# RF-VtoI.net
KiCad netlist of a schematic drawn in EAGLE
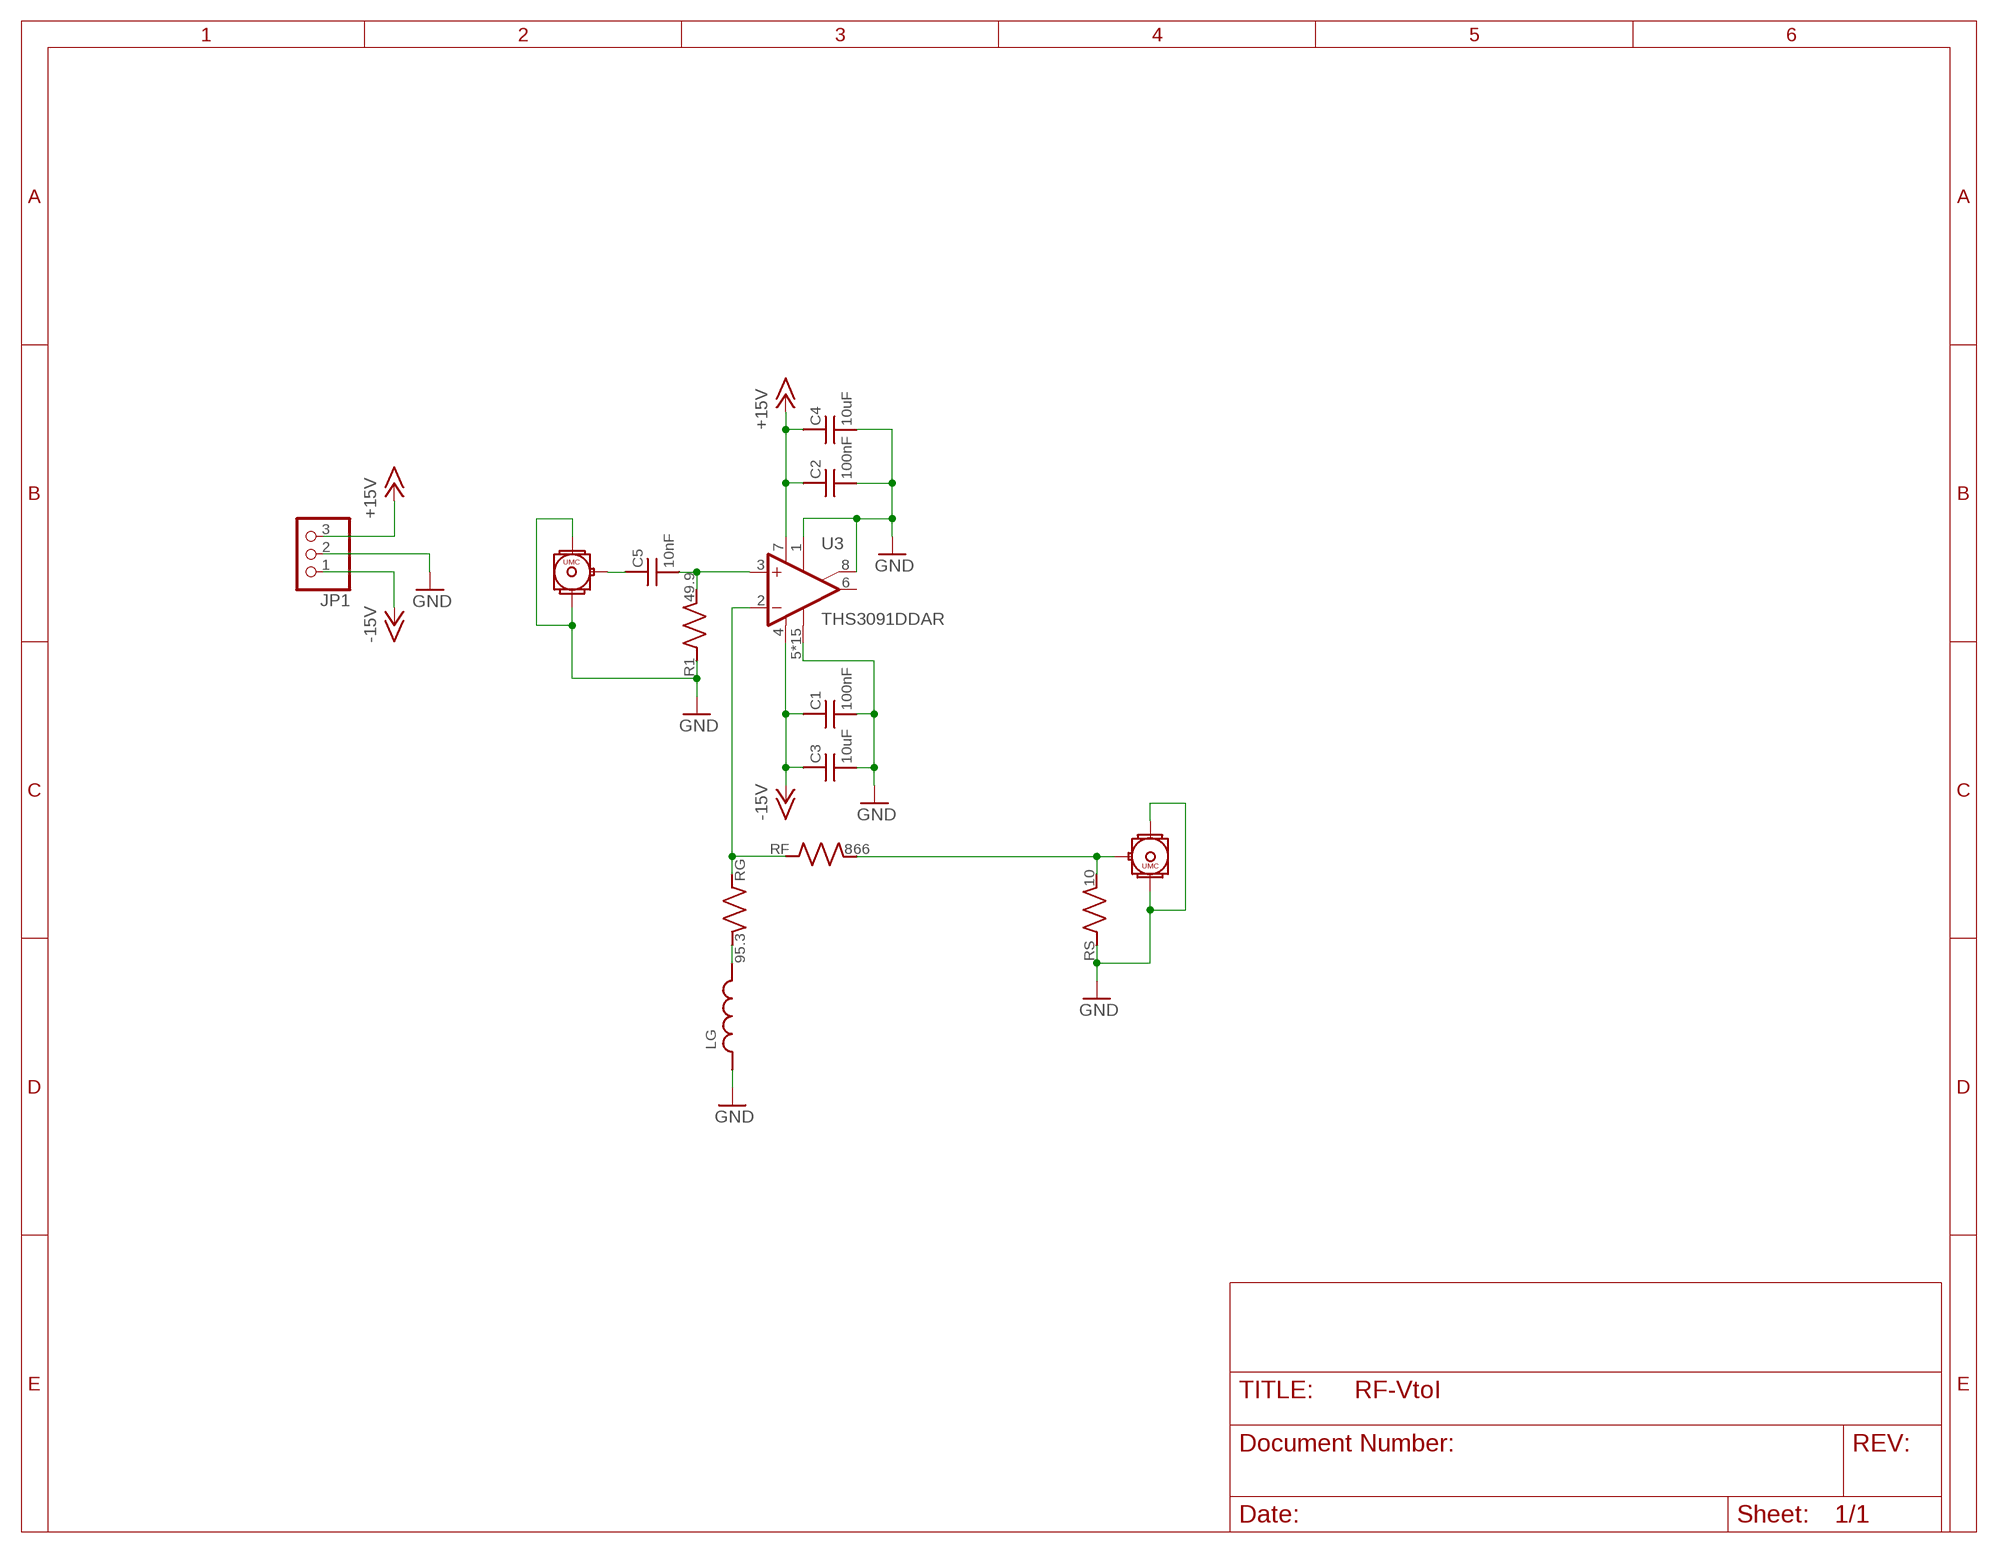
[diagram p0: schematic, sheet 1]

(export (version "E")
  (design (tool "Eeschema 10.0.6"))
  (components
    (comp (ref "C1")
      (value "100nF")
      (footprint "eagle-import:C_MLCC_0603")
      (fields (field (name "PARTNO") "06035C104K4Z2A"))
      (libsource (lib "eagle-import") (part "C_MLCC_SMDCMLCC_0603"))
    )
    (comp (ref "C2")
      (value "100nF")
      (footprint "eagle-import:C_MLCC_0603")
      (fields (field (name "PARTNO") "06035C104K4Z2A"))
      (libsource (lib "eagle-import") (part "C_MLCC_SMDCMLCC_0603"))
    )
    (comp (ref "C3")
      (value "10uF")
      (footprint "eagle-import:C_MLCC_1206")
      (fields (field (name "PARTNO") "C3216X5R1H106K160AB"))
      (libsource (lib "eagle-import") (part "C_MLCC_SMDCMLCC_1206"))
    )
    (comp (ref "C4")
      (value "10uF")
      (footprint "eagle-import:C_MLCC_1206")
      (fields (field (name "PARTNO") "C3216X5R1H106K160AB"))
      (libsource (lib "eagle-import") (part "C_MLCC_SMDCMLCC_1206"))
    )
    (comp (ref "C5")
      (value "10nF")
      (footprint "eagle-import:C_MLCC_0402")
      (fields (field (name "PARTNO") "CL05B103KB5NNNC"))
      (libsource (lib "eagle-import") (part "C_MLCC_SMDCMLCC_0402"))
    )
    (comp (ref "CON1")
      (value "UMC_CONNECTORREGULAR")
      (footprint "eagle-import:UMC_CONNECTOR")
      (fields (field (name "PARTNO") "1909763-1"))
      (libsource (lib "eagle-import") (part "UMC_CONNECTORREGULAR"))
    )
    (comp (ref "CON2")
      (value "UMC_CONNECTORREGULAR")
      (footprint "eagle-import:UMC_CONNECTOR")
      (fields (field (name "PARTNO") "1909763-1"))
      (libsource (lib "eagle-import") (part "UMC_CONNECTORREGULAR"))
    )
    (comp (ref "JP1")
      (value "PINHD-1X3")
      (footprint "eagle-import:1X03")
      (fields (field (name "PARTNO") "640456-3"))
      (libsource (lib "eagle-import") (part "PINHD-1X3"))
    )
    (comp (ref "LG")
      (value "L_FERRITE_SMD_1008")
      (footprint "eagle-import:1008")
      (libsource (lib "eagle-import") (part "L_FERRITE_SMD_1008"))
    )
    (comp (ref "R1")
      (value "49.9")
      (footprint "eagle-import:R_0402")
      (fields (field (name "PARTNO") "ERA-2AEB49R9X"))
      (libsource (lib "eagle-import") (part "R_SMDR0402"))
    )
    (comp (ref "RF")
      (value "866")
      (footprint "eagle-import:R_0603")
      (fields (field (name "PARTNO") "ERA-3AEB8660V"))
      (libsource (lib "eagle-import") (part "R_SMDR0603"))
    )
    (comp (ref "RG")
      (value "95.3")
      (footprint "eagle-import:R_0402")
      (fields (field (name "PARTNO") "ERA-2AEB95R3X"))
      (libsource (lib "eagle-import") (part "R_SMDR0402"))
    )
    (comp (ref "RS")
      (value "10")
      (footprint "eagle-import:R_1206")
      (fields (field (name "PARTNO") "PHP01206E10R0BST5"))
      (libsource (lib "eagle-import") (part "R_SMDR1206"))
    )
    (comp (ref "U3")
      (value "THS3091DDAR")
      (footprint "eagle-import:DDA8_2P28X2P28")
      (fields (field (name "MANUFACTURER") "Texas Instruments"))
      (libsource (lib "eagle-import") (part "THS3091DDAR"))
    )
  )
  (nets
    (net (code "1") (name "+15V") (class "Default")
      (node (ref "C2") (pin "P$1") (pinfunction "1_P$1") (pintype "passive"))
      (node (ref "C4") (pin "P$1") (pinfunction "1_P$1") (pintype "passive"))
      (node (ref "JP1") (pin "3") (pinfunction "3_3") (pintype "passive"))
      (node (ref "U3") (pin "7") (pinfunction "V+_7") (pintype "power_in"))
    )
    (net (code "2") (name "-15V") (class "Default")
      (node (ref "C1") (pin "P$1") (pinfunction "1_P$1") (pintype "passive"))
      (node (ref "C3") (pin "P$1") (pinfunction "1_P$1") (pintype "passive"))
      (node (ref "JP1") (pin "1") (pinfunction "1_1") (pintype "passive"))
      (node (ref "U3") (pin "4") (pinfunction "V-_4") (pintype "power_in"))
    )
    (net (code "3") (name "GND") (class "Default")
      (node (ref "C1") (pin "P$2") (pinfunction "2_P$2") (pintype "passive"))
      (node (ref "C2") (pin "P$2") (pinfunction "2_P$2") (pintype "passive"))
      (node (ref "C3") (pin "P$2") (pinfunction "2_P$2") (pintype "passive"))
      (node (ref "C4") (pin "P$2") (pinfunction "2_P$2") (pintype "passive"))
      (node (ref "CON1") (pin "P$2") (pinfunction "P$2_P$2") (pintype "bidirectional"))
      (node (ref "CON1") (pin "P$3") (pinfunction "P$3_P$3") (pintype "bidirectional"))
      (node (ref "CON2") (pin "P$2") (pinfunction "P$2_P$2") (pintype "bidirectional"))
      (node (ref "CON2") (pin "P$3") (pinfunction "P$3_P$3") (pintype "bidirectional"))
      (node (ref "JP1") (pin "2") (pinfunction "2_2") (pintype "passive"))
      (node (ref "LG") (pin "P$1") (pinfunction "1_P$1") (pintype "passive"))
      (node (ref "R1") (pin "P$1") (pinfunction "1_P$1") (pintype "passive"))
      (node (ref "RS") (pin "P$1") (pinfunction "1_P$1") (pintype "passive"))
      (node (ref "U3") (pin "1") (pinfunction "ON1_1") (pintype "passive"))
      (node (ref "U3") (pin "5") (pinfunction "OPT_5") (pintype "passive"))
      (node (ref "U3") (pin "8") (pinfunction "ON2_8") (pintype "passive"))
      (node (ref "U3") (pin "EPAD") (pinfunction "OPT_EPAD") (pintype "passive"))
      (node (ref "U3") (pin "P$1") (pinfunction "OPT_P$1") (pintype "passive"))
      (node (ref "U3") (pin "P$10") (pinfunction "OPT_P$10") (pintype "passive"))
      (node (ref "U3") (pin "P$11") (pinfunction "OPT_P$11") (pintype "passive"))
      (node (ref "U3") (pin "P$12") (pinfunction "OPT_P$12") (pintype "passive"))
      (node (ref "U3") (pin "P$13") (pinfunction "OPT_P$13") (pintype "passive"))
      (node (ref "U3") (pin "P$2") (pinfunction "OPT_P$2") (pintype "passive"))
      (node (ref "U3") (pin "P$3") (pinfunction "OPT_P$3") (pintype "passive"))
      (node (ref "U3") (pin "P$4") (pinfunction "OPT_P$4") (pintype "passive"))
      (node (ref "U3") (pin "P$5") (pinfunction "OPT_P$5") (pintype "passive"))
      (node (ref "U3") (pin "P$6") (pinfunction "OPT_P$6") (pintype "passive"))
      (node (ref "U3") (pin "P$7") (pinfunction "OPT_P$7") (pintype "passive"))
      (node (ref "U3") (pin "P$8") (pinfunction "OPT_P$8") (pintype "passive"))
      (node (ref "U3") (pin "P$9") (pinfunction "OPT_P$9") (pintype "passive"))
    )
    (net (code "4") (name "Net-(C5-1)") (class "Default")
      (node (ref "C5") (pin "P$1") (pinfunction "1_P$1") (pintype "passive"))
      (node (ref "CON2") (pin "P$1") (pinfunction "P$1_P$1") (pintype "bidirectional"))
    )
    (net (code "5") (name "Net-(C5-2)") (class "Default")
      (node (ref "C5") (pin "P$2") (pinfunction "2_P$2") (pintype "passive"))
      (node (ref "R1") (pin "P$2") (pinfunction "2_P$2") (pintype "passive"))
      (node (ref "U3") (pin "3") (pinfunction "+IN_3") (pintype "input"))
    )
    (net (code "6") (name "Net-(LG-2)") (class "Default")
      (node (ref "LG") (pin "P$2") (pinfunction "2_P$2") (pintype "passive"))
      (node (ref "RG") (pin "P$2") (pinfunction "2_P$2") (pintype "passive"))
    )
    (net (code "7") (name "Net-(RF-1)") (class "Default")
      (node (ref "RF") (pin "P$1") (pinfunction "1_P$1") (pintype "passive"))
      (node (ref "RG") (pin "P$1") (pinfunction "1_P$1") (pintype "passive"))
      (node (ref "U3") (pin "2") (pinfunction "-IN_2") (pintype "input"))
    )
    (net (code "8") (name "Net-(RF-2)") (class "Default")
      (node (ref "CON1") (pin "P$1") (pinfunction "P$1_P$1") (pintype "bidirectional"))
      (node (ref "RF") (pin "P$2") (pinfunction "2_P$2") (pintype "passive"))
      (node (ref "RS") (pin "P$2") (pinfunction "2_P$2") (pintype "passive"))
    )
    (net (code "9") (name "unconnected-(U3-OUT-Pad6)") (class "Default")
      (node (ref "U3") (pin "6") (pinfunction "OUT_6") (pintype "output"))
    )
  )
)
